# tca9406_breakout.net
KiCad netlist of a schematic drawn in EAGLE
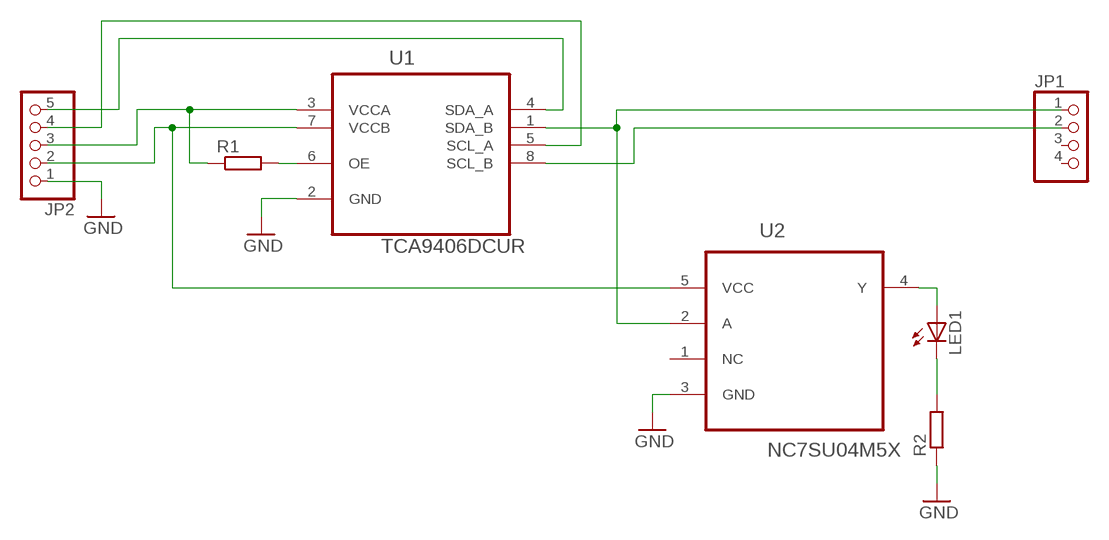
[diagram p0: schematic, sheet 1]

(export (version "E")
  (design (tool "Eeschema 10.0.6"))
  (components
    (comp (ref "JP1")
      (value "PINHD-1X4")
      (footprint "eagle-import:1X04")
      (libsource (lib "eagle-import") (part "PINHD-1X4"))
    )
    (comp (ref "JP2")
      (value "PINHD-1X5")
      (footprint "eagle-import:1X05")
      (libsource (lib "eagle-import") (part "PINHD-1X5"))
    )
    (comp (ref "LED1")
      (value "LEDSML1206")
      (footprint "eagle-import:SML1206")
      (libsource (lib "eagle-import") (part "LEDSML1206"))
    )
    (comp (ref "R1")
      (value "R-EU_M1406")
      (footprint "eagle-import:M1406")
      (libsource (lib "eagle-import") (part "R-EU_M1406"))
    )
    (comp (ref "R2")
      (value "R-EU_M1406")
      (footprint "eagle-import:M1406")
      (libsource (lib "eagle-import") (part "R-EU_M1406"))
    )
    (comp (ref "U1")
      (value "TCA9406DCUR")
      (footprint "eagle-import:SOP50P310X90-8N")
      (libsource (lib "eagle-import") (part "TCA9406DCUR"))
    )
    (comp (ref "U2")
      (value "NC7SU04M5X")
      (footprint "eagle-import:SOT95P280X145-5N")
      (libsource (lib "eagle-import") (part "NC7SU04M5X"))
    )
  )
  (nets
    (net (code "1") (name "GND") (class "Default")
      (node (ref "JP2") (pin "1") (pinfunction "1_1") (pintype "passive"))
      (node (ref "R2") (pin "1") (pinfunction "1_1") (pintype "passive"))
      (node (ref "U1") (pin "2") (pinfunction "GND_2") (pintype "power_in"))
      (node (ref "U2") (pin "3") (pinfunction "GND_3") (pintype "passive"))
    )
    (net (code "2") (name "Net-(LED1-PadC)") (class "Default")
      (node (ref "LED1") (pin "C") (pinfunction "C_C") (pintype "passive"))
      (node (ref "R2") (pin "2") (pinfunction "2_2") (pintype "passive"))
    )
    (net (code "3") (name "Net-(U1-OE)") (class "Default")
      (node (ref "R1") (pin "2") (pinfunction "2_2") (pintype "passive"))
      (node (ref "U1") (pin "6") (pinfunction "OE_6") (pintype "input"))
    )
    (net (code "4") (name "Net-(U1-SCL_A)") (class "Default")
      (node (ref "JP2") (pin "4") (pinfunction "4_4") (pintype "passive"))
      (node (ref "U1") (pin "5") (pinfunction "SCL_A_5") (pintype "bidirectional"))
    )
    (net (code "5") (name "Net-(U1-SCL_B)") (class "Default")
      (node (ref "JP1") (pin "2") (pinfunction "2_2") (pintype "passive"))
      (node (ref "U1") (pin "8") (pinfunction "SCL_B_8") (pintype "bidirectional"))
    )
    (net (code "6") (name "Net-(U1-SDA_A)") (class "Default")
      (node (ref "JP2") (pin "5") (pinfunction "5_5") (pintype "passive"))
      (node (ref "U1") (pin "4") (pinfunction "SDA_A_4") (pintype "bidirectional"))
    )
    (net (code "7") (name "Net-(U1-SDA_B)") (class "Default")
      (node (ref "JP1") (pin "1") (pinfunction "1_1") (pintype "passive"))
      (node (ref "U1") (pin "1") (pinfunction "SDA_B_1") (pintype "bidirectional"))
      (node (ref "U2") (pin "2") (pinfunction "A_2") (pintype "input"))
    )
    (net (code "8") (name "Net-(U1-VCCA)") (class "Default")
      (node (ref "JP2") (pin "3") (pinfunction "3_3") (pintype "passive"))
      (node (ref "R1") (pin "1") (pinfunction "1_1") (pintype "passive"))
      (node (ref "U1") (pin "3") (pinfunction "VCCA_3") (pintype "power_in"))
    )
    (net (code "9") (name "Net-(U1-VCCB)") (class "Default")
      (node (ref "JP2") (pin "2") (pinfunction "2_2") (pintype "passive"))
      (node (ref "U1") (pin "7") (pinfunction "VCCB_7") (pintype "power_in"))
      (node (ref "U2") (pin "5") (pinfunction "VCC_5") (pintype "power_in"))
    )
    (net (code "10") (name "Net-(U2-Y)") (class "Default")
      (node (ref "LED1") (pin "A") (pinfunction "A_A") (pintype "passive"))
      (node (ref "U2") (pin "4") (pinfunction "Y_4") (pintype "output"))
    )
    (net (code "11") (name "unconnected-(JP1-Pad3)") (class "Default")
      (node (ref "JP1") (pin "3") (pinfunction "3_3") (pintype "passive"))
    )
    (net (code "12") (name "unconnected-(JP1-Pad4)") (class "Default")
      (node (ref "JP1") (pin "4") (pinfunction "4_4") (pintype "passive"))
    )
    (net (code "13") (name "unconnected-(U2-NC-Pad1)") (class "Default")
      (node (ref "U2") (pin "1") (pinfunction "NC_1") (pintype "no_connect"))
    )
  )
)
